# Adafruit_Si7021_Temperature_and_Humidity.net
KiCad netlist of a schematic drawn in EAGLE
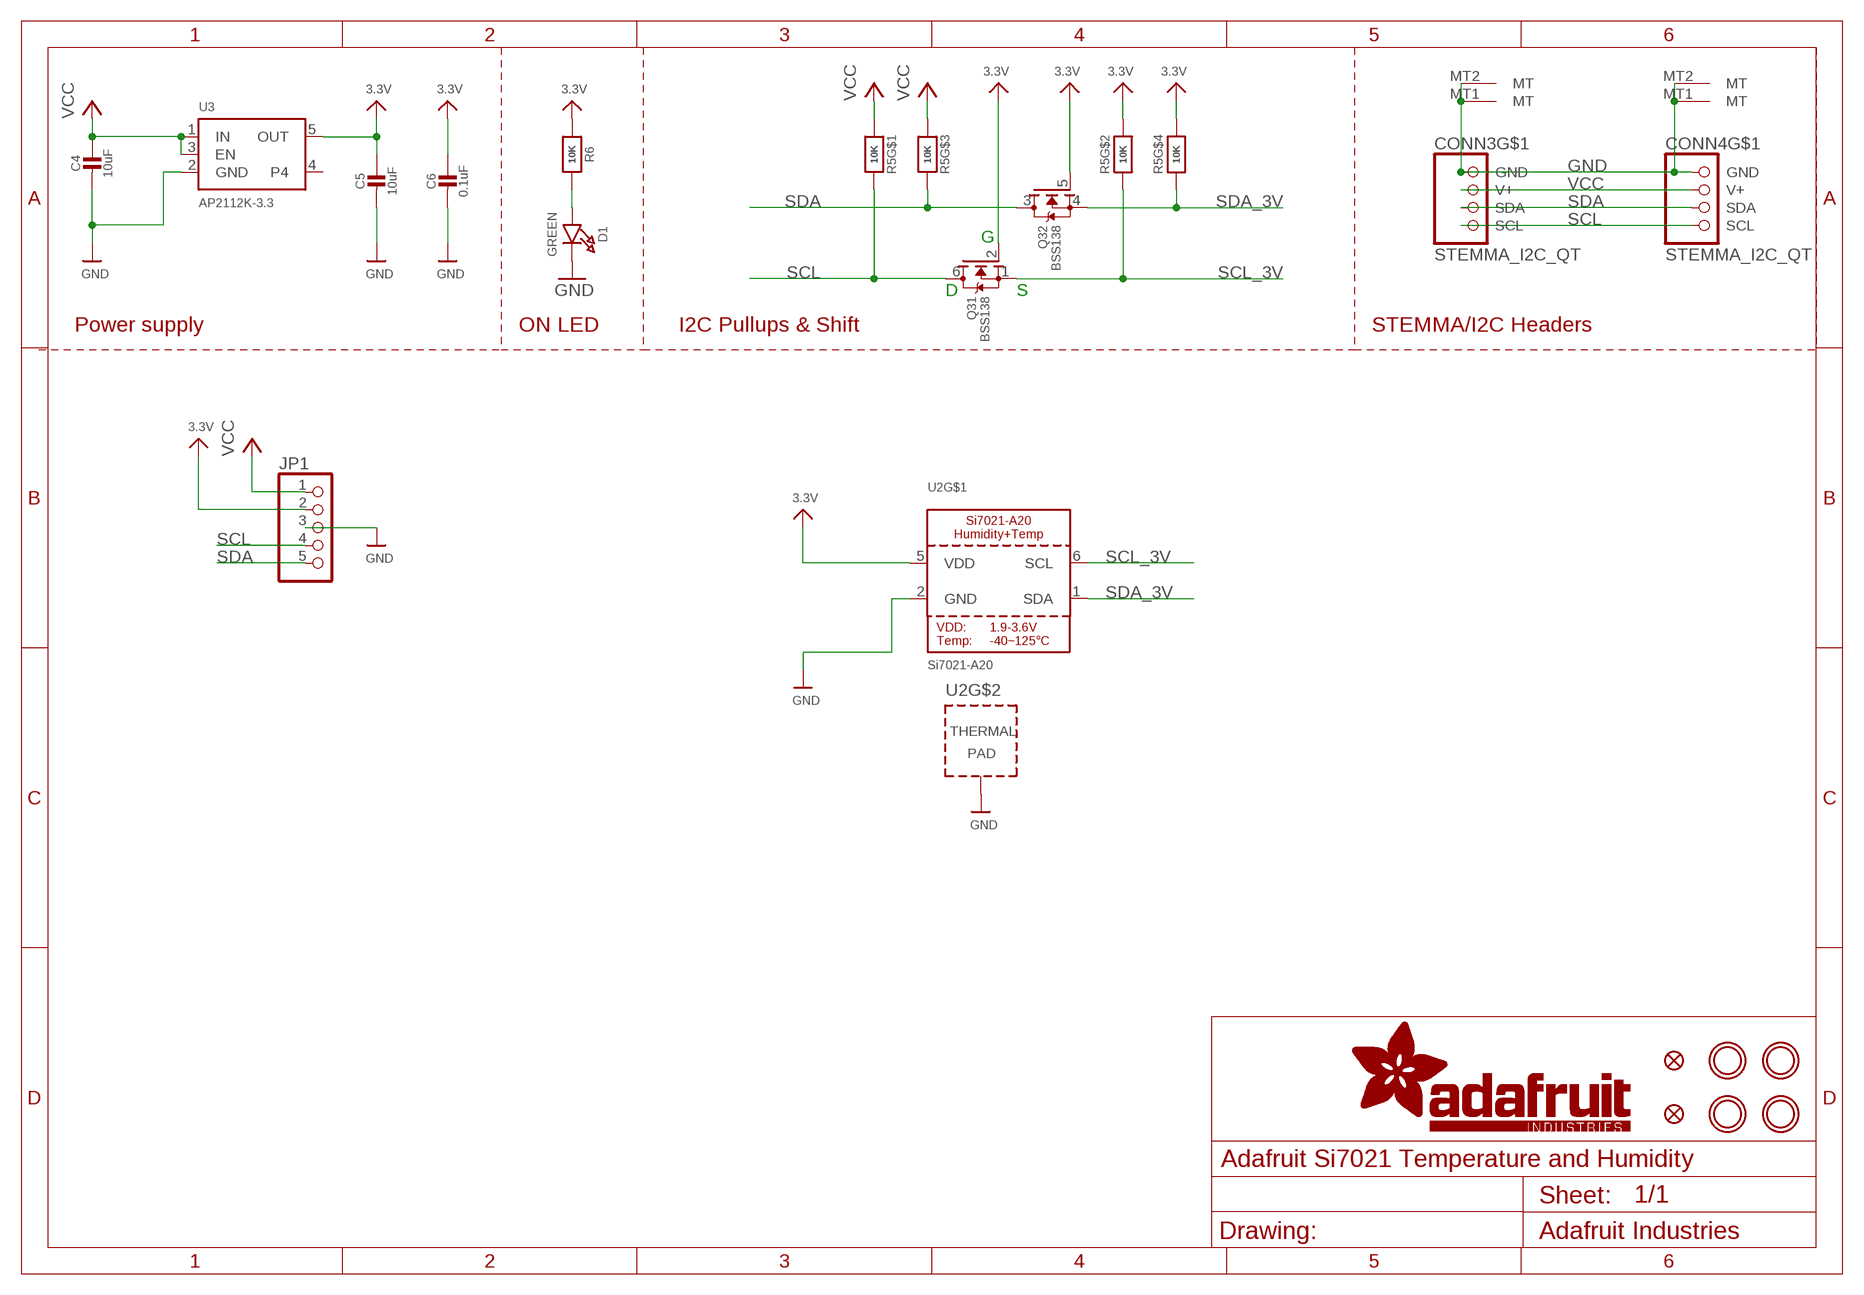
[diagram p0: schematic, sheet 1]

(export (version "E")
  (design (tool "Eeschema 10.0.6"))
  (components
    (comp (ref "C4")
      (value "10uF")
      (footprint "eagle-import:0805-NO")
      (libsource (lib "eagle-import") (part "CAP_CERAMIC0805-NOOUTLINE"))
    )
    (comp (ref "C5")
      (value "10uF")
      (footprint "eagle-import:0805-NO")
      (libsource (lib "eagle-import") (part "CAP_CERAMIC0805-NOOUTLINE"))
    )
    (comp (ref "C6")
      (value "0.1uF")
      (footprint "eagle-import:0603-NO")
      (libsource (lib "eagle-import") (part "CAP_CERAMIC0603_NO"))
    )
    (comp (ref "CONN3")
      (value "STEMMA_I2C_QT")
      (footprint "eagle-import:JST_SH4")
      (libsource (lib "eagle-import") (part "STEMMA_I2C_QT"))
    )
    (comp (ref "CONN4")
      (value "STEMMA_I2C_QT")
      (footprint "eagle-import:JST_SH4")
      (libsource (lib "eagle-import") (part "STEMMA_I2C_QT"))
    )
    (comp (ref "D1")
      (value "GREEN")
      (footprint "eagle-import:CHIPLED_0603_NOOUTLINE")
      (libsource (lib "eagle-import") (part "LED0603_NOOUTLINE"))
    )
    (comp (ref "FID3")
      (value "FIDUCIAL_1MM")
      (footprint "eagle-import:FIDUCIAL_1MM")
      (libsource (lib "eagle-import") (part "FIDUCIAL_1MM"))
    )
    (comp (ref "FID4")
      (value "FIDUCIAL_1MM")
      (footprint "eagle-import:FIDUCIAL_1MM")
      (libsource (lib "eagle-import") (part "FIDUCIAL_1MM"))
    )
    (comp (ref "JP1")
      (value "HEADER-1X570MIL")
      (footprint "eagle-import:1X05_ROUND_70")
      (libsource (lib "eagle-import") (part "HEADER-1X570MIL"))
    )
    (comp (ref "Q3")
      (value "BSS138")
      (footprint "eagle-import:SOT363")
      (libsource (lib "eagle-import") (part "MOSFET-N_DUAL"))
    )
    (comp (ref "R5")
      (value "10K")
      (footprint "eagle-import:RESPACK_4X0603")
      (libsource (lib "eagle-import") (part "RESISTOR_4PACK"))
    )
    (comp (ref "R6")
      (value "10K")
      (footprint "eagle-import:0603-NO")
      (libsource (lib "eagle-import") (part "RESISTOR_0603_NOOUT"))
    )
    (comp (ref "U$19")
      (value "MOUNTINGHOLE2.5")
      (footprint "eagle-import:MOUNTINGHOLE_2.5_PLATED")
      (libsource (lib "eagle-import") (part "MOUNTINGHOLE2.5"))
    )
    (comp (ref "U$20")
      (value "MOUNTINGHOLE2.5")
      (footprint "eagle-import:MOUNTINGHOLE_2.5_PLATED")
      (libsource (lib "eagle-import") (part "MOUNTINGHOLE2.5"))
    )
    (comp (ref "U$22")
      (value "MOUNTINGHOLE2.5")
      (footprint "eagle-import:MOUNTINGHOLE_2.5_PLATED")
      (libsource (lib "eagle-import") (part "MOUNTINGHOLE2.5"))
    )
    (comp (ref "U$25")
      (value "MOUNTINGHOLE2.5")
      (footprint "eagle-import:MOUNTINGHOLE_2.5_PLATED")
      (libsource (lib "eagle-import") (part "MOUNTINGHOLE2.5"))
    )
    (comp (ref "U2")
      (value "Si7021-A20")
      (footprint "eagle-import:DFN6_3X3_SI")
      (libsource (lib "eagle-import") (part "SI7021-A20"))
    )
    (comp (ref "U3")
      (value "AP2112K-3.3")
      (footprint "eagle-import:SOT23-5")
      (libsource (lib "eagle-import") (part "VREG_SOT23-5"))
    )
  )
  (nets
    (net (code "1") (name "/SCL") (class "Default")
      (node (ref "CONN3") (pin "4") (pinfunction "SCL_4") (pintype "passive"))
      (node (ref "CONN4") (pin "4") (pinfunction "SCL_4") (pintype "passive"))
      (node (ref "JP1") (pin "4") (pinfunction "4_4") (pintype "passive"))
      (node (ref "Q3") (pin "6") (pinfunction "D_6") (pintype "bidirectional"))
      (node (ref "R5") (pin "8") (pinfunction "2_8") (pintype "passive"))
    )
    (net (code "2") (name "/SCL_3V") (class "Default")
      (node (ref "Q3") (pin "1") (pinfunction "S_1") (pintype "bidirectional"))
      (node (ref "R5") (pin "7") (pinfunction "2_7") (pintype "passive"))
      (node (ref "U2") (pin "6") (pinfunction "SCL_6") (pintype "open_collector"))
    )
    (net (code "3") (name "/SDA") (class "Default")
      (node (ref "CONN3") (pin "3") (pinfunction "SDA_3") (pintype "passive"))
      (node (ref "CONN4") (pin "3") (pinfunction "SDA_3") (pintype "passive"))
      (node (ref "JP1") (pin "5") (pinfunction "5_5") (pintype "passive"))
      (node (ref "Q3") (pin "3") (pinfunction "D_3") (pintype "bidirectional"))
      (node (ref "R5") (pin "6") (pinfunction "2_6") (pintype "passive"))
    )
    (net (code "4") (name "/SDA_3V") (class "Default")
      (node (ref "Q3") (pin "4") (pinfunction "S_4") (pintype "bidirectional"))
      (node (ref "R5") (pin "5") (pinfunction "2_5") (pintype "passive"))
      (node (ref "U2") (pin "1") (pinfunction "SDA_1") (pintype "open_collector"))
    )
    (net (code "5") (name "3.3V") (class "Default")
      (node (ref "C5") (pin "1") (pinfunction "1_1") (pintype "passive"))
      (node (ref "C6") (pin "1") (pinfunction "1_1") (pintype "passive"))
      (node (ref "JP1") (pin "2") (pinfunction "2_2") (pintype "passive"))
      (node (ref "Q3") (pin "2") (pinfunction "G_2") (pintype "bidirectional"))
      (node (ref "Q3") (pin "5") (pinfunction "G_5") (pintype "bidirectional"))
      (node (ref "R5") (pin "2") (pinfunction "1_2") (pintype "passive"))
      (node (ref "R5") (pin "4") (pinfunction "1_4") (pintype "passive"))
      (node (ref "R6") (pin "1") (pinfunction "1_1") (pintype "passive"))
      (node (ref "U2") (pin "5") (pinfunction "VDD_5") (pintype "power_in"))
      (node (ref "U3") (pin "5") (pinfunction "OUT_5") (pintype "power_in"))
    )
    (net (code "6") (name "GND") (class "Default")
      (node (ref "C4") (pin "2") (pinfunction "2_2") (pintype "passive"))
      (node (ref "C5") (pin "2") (pinfunction "2_2") (pintype "passive"))
      (node (ref "C6") (pin "2") (pinfunction "2_2") (pintype "passive"))
      (node (ref "CONN3") (pin "1") (pinfunction "GND_1") (pintype "passive"))
      (node (ref "CONN3") (pin "MT1") (pinfunction "MT_MT1") (pintype "bidirectional"))
      (node (ref "CONN3") (pin "MT2") (pinfunction "MT_MT2") (pintype "bidirectional"))
      (node (ref "CONN4") (pin "1") (pinfunction "GND_1") (pintype "passive"))
      (node (ref "CONN4") (pin "MT1") (pinfunction "MT_MT1") (pintype "bidirectional"))
      (node (ref "CONN4") (pin "MT2") (pinfunction "MT_MT2") (pintype "bidirectional"))
      (node (ref "D1") (pin "C") (pinfunction "C_C") (pintype "passive"))
      (node (ref "JP1") (pin "3") (pinfunction "3_3") (pintype "passive"))
      (node (ref "U2") (pin "2") (pinfunction "GND_2") (pintype "power_in"))
      (node (ref "U2") (pin "PAD") (pinfunction "TP_PAD") (pintype "power_in"))
      (node (ref "U3") (pin "2") (pinfunction "GND_2") (pintype "power_in"))
    )
    (net (code "7") (name "Net-(D1-PadA)") (class "Default")
      (node (ref "D1") (pin "A") (pinfunction "A_A") (pintype "passive"))
      (node (ref "R6") (pin "2") (pinfunction "2_2") (pintype "passive"))
    )
    (net (code "8") (name "VCC") (class "Default")
      (node (ref "C4") (pin "1") (pinfunction "1_1") (pintype "passive"))
      (node (ref "CONN3") (pin "2") (pinfunction "V+_2") (pintype "passive"))
      (node (ref "CONN4") (pin "2") (pinfunction "V+_2") (pintype "passive"))
      (node (ref "JP1") (pin "1") (pinfunction "1_1") (pintype "passive"))
      (node (ref "R5") (pin "1") (pinfunction "1_1") (pintype "passive"))
      (node (ref "R5") (pin "3") (pinfunction "1_3") (pintype "passive"))
      (node (ref "U3") (pin "1") (pinfunction "IN_1") (pintype "power_in"))
      (node (ref "U3") (pin "3") (pinfunction "EN_3") (pintype "input"))
    )
    (net (code "9") (name "unconnected-(U3-P4-Pad4)") (class "Default")
      (node (ref "U3") (pin "4") (pinfunction "P4_4") (pintype "bidirectional"))
    )
  )
)
